# microSD_reader.net
KiCad netlist of a schematic drawn in Altium Designer
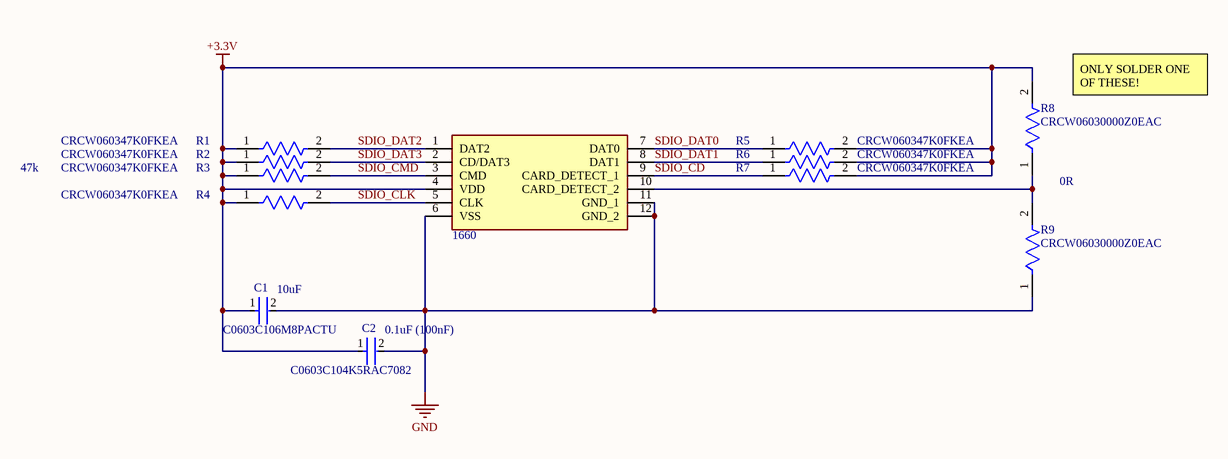
[diagram p0: microSD_reader.SchDoc]

(export (version "E")
  (design (tool "Eeschema 10.0.6"))
  (components
    (comp (ref "C1")
      (value "C0603C106M8PACTU")
      (footprint "FP-C0603C106M8PACTU-MFG")
      (description "CAP CER 10UF 10V X5R 0603")
      (libsource (lib "Altium Content Vault") (part "02cd4be3c70576c341d710602a673aa"))
    )
    (comp (ref "C2")
      (value "C0603C104K5RAC7082")
      (footprint "FP-C0603C-CF-MFG")
      (description "C0603 0.10 μF X7R 30ppm/°C 10.00% 50 V")
      (fields
        (field (name "OCTOPART") "https://octopart.com/c0603c104k5rac7082-kemet-75146597")
        (field (name "MANUFACTURER") "KEMET")
      )
      (libsource (lib "Altium Content Vault") (part "b4654b650e69147ec39a6b967a45e02"))
    )
    (comp (ref "J1")
      (value "1660")
      (footprint "1660")
      (description "Adafruit Accessories MIcroSD Socket")
      (fields (field (name "MOUSER PART NUMBER") "485-1660"))
      (libsource (lib "1660") (part "1660"))
    )
    (comp (ref "R1")
      (value "CRCW060347K0FKEA")
      (footprint "FP-CRCW0603-e3-IPC_B")
      (description "RES SMD 47K OHM 1% 1/10W 0603")
      (fields (field (name "TOLERANCE") "1%"))
      (libsource (lib "Altium Content Vault") (part "1029c3af85768c4190bb7ad29bc67b5"))
    )
    (comp (ref "R2")
      (value "CRCW060347K0FKEA")
      (footprint "FP-CRCW0603-e3-IPC_B")
      (description "RES SMD 47K OHM 1% 1/10W 0603")
      (fields (field (name "TOLERANCE") "1%"))
      (libsource (lib "Altium Content Vault") (part "1029c3af85768c4190bb7ad29bc67b5"))
    )
    (comp (ref "R3")
      (value "CRCW060347K0FKEA")
      (footprint "FP-CRCW0603-e3-IPC_B")
      (description "RES SMD 47K OHM 1% 1/10W 0603")
      (fields (field (name "TOLERANCE") "1%"))
      (libsource (lib "Altium Content Vault") (part "1029c3af85768c4190bb7ad29bc67b5"))
    )
    (comp (ref "R4")
      (value "CRCW060347K0FKEA")
      (footprint "FP-CRCW0603-e3-IPC_B")
      (description "RES SMD 47K OHM 1% 1/10W 0603")
      (fields (field (name "TOLERANCE") "1%"))
      (libsource (lib "Altium Content Vault") (part "1029c3af85768c4190bb7ad29bc67b5"))
    )
    (comp (ref "R5")
      (value "CRCW060347K0FKEA")
      (footprint "FP-CRCW0603-e3-IPC_B")
      (description "RES SMD 47K OHM 1% 1/10W 0603")
      (fields (field (name "TOLERANCE") "1%"))
      (libsource (lib "Altium Content Vault") (part "1029c3af85768c4190bb7ad29bc67b5"))
    )
    (comp (ref "R6")
      (value "CRCW060347K0FKEA")
      (footprint "FP-CRCW0603-e3-IPC_B")
      (description "RES SMD 47K OHM 1% 1/10W 0603")
      (fields (field (name "TOLERANCE") "1%"))
      (libsource (lib "Altium Content Vault") (part "1029c3af85768c4190bb7ad29bc67b5"))
    )
    (comp (ref "R7")
      (value "CRCW060347K0FKEA")
      (footprint "FP-CRCW0603-e3-IPC_B")
      (description "RES SMD 47K OHM 1% 1/10W 0603")
      (fields (field (name "TOLERANCE") "1%"))
      (libsource (lib "Altium Content Vault") (part "1029c3af85768c4190bb7ad29bc67b5"))
    )
    (comp (ref "R8")
      (value "CRCW06030000Z0EAC")
      (footprint "FP-CRCW0603-C-IPC_B")
      (description "RES 0 OHM JUMPER 1/10W 0603")
      (libsource (lib "Altium Content Vault") (part "1029c3af85768c4190bb7ad29bc67b5"))
    )
    (comp (ref "R9")
      (value "CRCW06030000Z0EAC")
      (footprint "FP-CRCW0603-C-IPC_B")
      (description "RES 0 OHM JUMPER 1/10W 0603")
      (libsource (lib "Altium Content Vault") (part "1029c3af85768c4190bb7ad29bc67b5"))
    )
  )
  (nets
    (net (code "1") (name "+3.3V") (class "Default")
      (node (ref "C1") (pin "1") (pinfunction "1_1") (pintype "passive"))
      (node (ref "C2") (pin "1") (pinfunction "1_1") (pintype "passive"))
      (node (ref "J1") (pin "4") (pinfunction "VDD_4") (pintype "passive"))
      (node (ref "R1") (pin "1") (pinfunction "1_1") (pintype "passive"))
      (node (ref "R2") (pin "1") (pinfunction "1_1") (pintype "passive"))
      (node (ref "R3") (pin "1") (pinfunction "1_1") (pintype "passive"))
      (node (ref "R4") (pin "1") (pinfunction "1_1") (pintype "passive"))
      (node (ref "R5") (pin "2") (pinfunction "2_2") (pintype "passive"))
      (node (ref "R6") (pin "2") (pinfunction "2_2") (pintype "passive"))
      (node (ref "R7") (pin "2") (pinfunction "2_2") (pintype "passive"))
      (node (ref "R8") (pin "2") (pinfunction "2_2") (pintype "passive"))
    )
    (net (code "2") (name "/SDIO_CD") (class "Default")
      (node (ref "J1") (pin "9") (pinfunction "CARD_DETECT_1_9") (pintype "passive"))
      (node (ref "R7") (pin "1") (pinfunction "1_1") (pintype "passive"))
    )
    (net (code "3") (name "/SDIO_CLK") (class "Default")
      (node (ref "J1") (pin "5") (pinfunction "CLK_5") (pintype "passive"))
      (node (ref "R4") (pin "2") (pinfunction "2_2") (pintype "passive"))
    )
    (net (code "4") (name "/SDIO_CMD") (class "Default")
      (node (ref "J1") (pin "3") (pinfunction "CMD_3") (pintype "passive"))
      (node (ref "R3") (pin "2") (pinfunction "2_2") (pintype "passive"))
    )
    (net (code "5") (name "/SDIO_DAT0") (class "Default")
      (node (ref "J1") (pin "7") (pinfunction "DAT0_7") (pintype "passive"))
      (node (ref "R5") (pin "1") (pinfunction "1_1") (pintype "passive"))
    )
    (net (code "6") (name "/SDIO_DAT1") (class "Default")
      (node (ref "J1") (pin "8") (pinfunction "DAT1_8") (pintype "passive"))
      (node (ref "R6") (pin "1") (pinfunction "1_1") (pintype "passive"))
    )
    (net (code "7") (name "/SDIO_DAT2") (class "Default")
      (node (ref "J1") (pin "1") (pinfunction "DAT2_1") (pintype "passive"))
      (node (ref "R1") (pin "2") (pinfunction "2_2") (pintype "passive"))
    )
    (net (code "8") (name "/SDIO_DAT3") (class "Default")
      (node (ref "J1") (pin "2") (pinfunction "CD/DAT3_2") (pintype "passive"))
      (node (ref "R2") (pin "2") (pinfunction "2_2") (pintype "passive"))
    )
    (net (code "9") (name "GND") (class "Default")
      (node (ref "C1") (pin "2") (pinfunction "2_2") (pintype "passive"))
      (node (ref "C2") (pin "2") (pinfunction "2_2") (pintype "passive"))
      (node (ref "J1") (pin "11") (pinfunction "GND_1_11") (pintype "passive"))
      (node (ref "J1") (pin "12") (pinfunction "GND_2_12") (pintype "passive"))
      (node (ref "J1") (pin "6") (pinfunction "VSS_6") (pintype "passive"))
      (node (ref "R9") (pin "1") (pinfunction "1_1") (pintype "passive"))
    )
    (net (code "10") (name "Net-(J1-CARD_DETECT_2)") (class "Default")
      (node (ref "J1") (pin "10") (pinfunction "CARD_DETECT_2_10") (pintype "passive"))
      (node (ref "R8") (pin "1") (pinfunction "1_1") (pintype "passive"))
      (node (ref "R9") (pin "2") (pinfunction "2_2") (pintype "passive"))
    )
  )
)
